# schema.net
KiCad netlist of a schematic drawn in EasyEDA
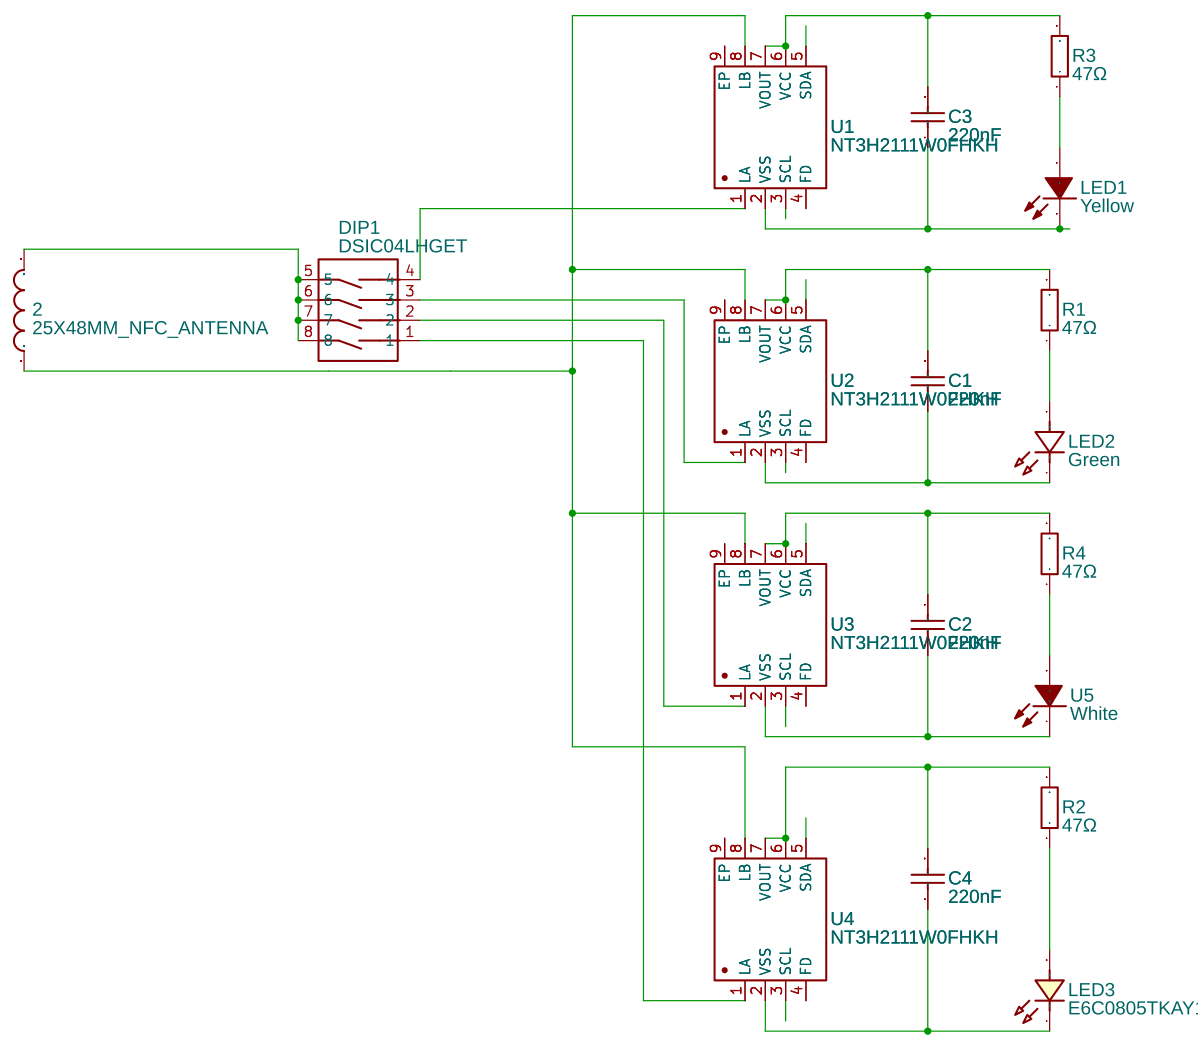
[diagram p0: schematic sheet]

(export (version "E")
  (design (tool "Eeschema 10.0.6"))
  (components
    (comp (ref "2") (value "25X48MM_NFC_ANTENNA") (libsource (lib "") (part "25X48MM_NFC_ANTENNA")))
    (comp (ref "C1")
      (value "220nF")
      (fields
        (field (name "Manufacturer Part") "CL10B224KA8NNNC")
        (field (name "Manufacturer") "SAMSUNG(三星)")
      )
      (libsource (lib "") (part "CL10B224KA8NNNC"))
    )
    (comp (ref "C2")
      (value "220nF")
      (fields
        (field (name "Manufacturer Part") "CL10B224KA8NNNC")
        (field (name "Manufacturer") "SAMSUNG(三星)")
      )
      (libsource (lib "") (part "CL10B224KA8NNNC"))
    )
    (comp (ref "C3")
      (value "220nF")
      (fields
        (field (name "Manufacturer Part") "CL10B224KA8NNNC")
        (field (name "Manufacturer") "SAMSUNG(三星)")
      )
      (libsource (lib "") (part "CL10B224KA8NNNC"))
    )
    (comp (ref "C4")
      (value "220nF")
      (fields
        (field (name "Manufacturer Part") "CL10B224KA8NNNC")
        (field (name "Manufacturer") "SAMSUNG(三星)")
      )
      (libsource (lib "") (part "CL10B224KA8NNNC"))
    )
    (comp (ref "DIP1")
      (value "DSIC04LHGET")
      (fields (field (name "Manufacturer") "YE"))
      (libsource (lib "") (part "DSIC04LHGET"))
    )
    (comp (ref "LED1")
      (value "Yellow")
      (fields (field (name "Manufacturer Part") "KT-0805黄灯") (field (name "Manufacturer") "KENTO"))
      (libsource (lib "") (part "17-21SUYC/TR8"))
    )
    (comp (ref "LED2")
      (value "Green")
      (fields (field (name "Manufacturer Part") "绿色0805封装贴片LED灯"))
      (libsource (lib "") (part "绿色0805封装贴片LED灯"))
    )
    (comp (ref "LED3")
      (value "E6C0805TKAY1UDA")
      (fields (field (name "Manufacturer") "ekinglux(亿晶源)"))
      (libsource (lib "") (part "E6C0805TKAY1UDA"))
    )
    (comp (ref "R1")
      (value "47Ω")
      (fields
        (field (name "Manufacturer Part") "0603WAF470JT5E")
        (field (name "Manufacturer") "UNI-ROYAL(厚声)")
      )
      (libsource (lib "") (part "0603WAF470JT5E"))
    )
    (comp (ref "R2")
      (value "47Ω")
      (fields
        (field (name "Manufacturer Part") "0603WAF470JT5E")
        (field (name "Manufacturer") "UNI-ROYAL(厚声)")
      )
      (libsource (lib "") (part "0603WAF470JT5E"))
    )
    (comp (ref "R3")
      (value "47Ω")
      (fields
        (field (name "Manufacturer Part") "0603WAF470JT5E")
        (field (name "Manufacturer") "UNI-ROYAL(厚声)")
      )
      (libsource (lib "") (part "0603WAF470JT5E"))
    )
    (comp (ref "R4")
      (value "47Ω")
      (fields
        (field (name "Manufacturer Part") "0603WAF470JT5E")
        (field (name "Manufacturer") "UNI-ROYAL(厚声)")
      )
      (libsource (lib "") (part "0603WAF470JT5E"))
    )
    (comp (ref "U1")
      (value "NT3H2111W0FHKH")
      (fields (field (name "Manufacturer") "NXP(恩智浦)"))
      (libsource (lib "") (part "NT3H2111W0FHKH"))
    )
    (comp (ref "U2")
      (value "NT3H2111W0FHKH")
      (fields (field (name "Manufacturer") "NXP(恩智浦)"))
      (libsource (lib "") (part "NT3H2111W0FHKH"))
    )
    (comp (ref "U3")
      (value "NT3H2111W0FHKH")
      (fields (field (name "Manufacturer") "NXP(恩智浦)"))
      (libsource (lib "") (part "NT3H2111W0FHKH"))
    )
    (comp (ref "U4")
      (value "NT3H2111W0FHKH")
      (fields (field (name "Manufacturer") "NXP(恩智浦)"))
      (libsource (lib "") (part "NT3H2111W0FHKH"))
    )
    (comp (ref "U5") (value "White") (libsource (lib "") (part "白光0805LED")))
  )
  (nets
    (net (code "1") (name "Net-(2-PadP$2)") (class "Default")
      (node (ref "2") (pin "P$2") (pinfunction "P$2_P$2") (pintype "bidirectional"))
      (node (ref "DIP1") (pin "5") (pinfunction "5_5") (pintype "unspecified"))
      (node (ref "DIP1") (pin "6") (pinfunction "6_6") (pintype "unspecified"))
      (node (ref "DIP1") (pin "7") (pinfunction "7_7") (pintype "unspecified"))
      (node (ref "DIP1") (pin "8") (pinfunction "8_8") (pintype "unspecified"))
    )
    (net (code "2") (name "Net-(LED1-+)") (class "Default")
      (node (ref "LED1") (pin "1") (pinfunction "+_1") (pintype "unspecified"))
      (node (ref "R3") (pin "1") (pinfunction "1_1") (pintype "input"))
    )
    (net (code "3") (name "Net-(LED1--)") (class "Default")
      (node (ref "C3") (pin "1") (pinfunction "1_1") (pintype "input"))
      (node (ref "LED1") (pin "2") (pinfunction "-_2") (pintype "unspecified"))
      (node (ref "U1") (pin "2") (pinfunction "VSS_2") (pintype "unspecified"))
    )
    (net (code "4") (name "Net-(LED2-A)") (class "Default")
      (node (ref "LED2") (pin "2") (pinfunction "A_2") (pintype "unspecified"))
      (node (ref "R1") (pin "1") (pinfunction "1_1") (pintype "input"))
    )
    (net (code "5") (name "Net-(LED2-K)") (class "Default")
      (node (ref "C1") (pin "1") (pinfunction "1_1") (pintype "input"))
      (node (ref "LED2") (pin "1") (pinfunction "K_1") (pintype "unspecified"))
      (node (ref "U2") (pin "2") (pinfunction "VSS_2") (pintype "unspecified"))
    )
    (net (code "6") (name "Net-(LED3-A)") (class "Default")
      (node (ref "LED3") (pin "2") (pinfunction "A_2") (pintype "unspecified"))
      (node (ref "R2") (pin "1") (pinfunction "1_1") (pintype "input"))
    )
    (net (code "7") (name "Net-(LED3-K)") (class "Default")
      (node (ref "C4") (pin "1") (pinfunction "1_1") (pintype "input"))
      (node (ref "LED3") (pin "1") (pinfunction "K_1") (pintype "unspecified"))
      (node (ref "U4") (pin "2") (pinfunction "VSS_2") (pintype "unspecified"))
    )
    (net (code "8") (name "Net-(U1-LA)") (class "Default")
      (node (ref "DIP1") (pin "4") (pinfunction "4_4") (pintype "unspecified"))
      (node (ref "U1") (pin "1") (pinfunction "LA_1") (pintype "unspecified"))
    )
    (net (code "9") (name "Net-(U1-LB)") (class "Default")
      (node (ref "2") (pin "P$1") (pinfunction "P$1_P$1") (pintype "bidirectional"))
      (node (ref "U1") (pin "8") (pinfunction "LB_8") (pintype "unspecified"))
      (node (ref "U2") (pin "8") (pinfunction "LB_8") (pintype "unspecified"))
      (node (ref "U3") (pin "8") (pinfunction "LB_8") (pintype "unspecified"))
      (node (ref "U4") (pin "8") (pinfunction "LB_8") (pintype "unspecified"))
    )
    (net (code "10") (name "Net-(U1-VCC)") (class "Default")
      (node (ref "C3") (pin "2") (pinfunction "2_2") (pintype "input"))
      (node (ref "R3") (pin "2") (pinfunction "2_2") (pintype "input"))
      (node (ref "U1") (pin "6") (pinfunction "VCC_6") (pintype "unspecified"))
      (node (ref "U1") (pin "7") (pinfunction "VOUT_7") (pintype "unspecified"))
    )
    (net (code "11") (name "Net-(U2-LA)") (class "Default")
      (node (ref "DIP1") (pin "3") (pinfunction "3_3") (pintype "unspecified"))
      (node (ref "U2") (pin "1") (pinfunction "LA_1") (pintype "unspecified"))
    )
    (net (code "12") (name "Net-(U2-VCC)") (class "Default")
      (node (ref "C1") (pin "2") (pinfunction "2_2") (pintype "input"))
      (node (ref "R1") (pin "2") (pinfunction "2_2") (pintype "input"))
      (node (ref "U2") (pin "6") (pinfunction "VCC_6") (pintype "unspecified"))
      (node (ref "U2") (pin "7") (pinfunction "VOUT_7") (pintype "unspecified"))
    )
    (net (code "13") (name "Net-(U3-LA)") (class "Default")
      (node (ref "DIP1") (pin "2") (pinfunction "2_2") (pintype "unspecified"))
      (node (ref "U3") (pin "1") (pinfunction "LA_1") (pintype "unspecified"))
    )
    (net (code "14") (name "Net-(U3-VCC)") (class "Default")
      (node (ref "C2") (pin "2") (pinfunction "2_2") (pintype "input"))
      (node (ref "R4") (pin "2") (pinfunction "2_2") (pintype "input"))
      (node (ref "U3") (pin "6") (pinfunction "VCC_6") (pintype "unspecified"))
      (node (ref "U3") (pin "7") (pinfunction "VOUT_7") (pintype "unspecified"))
    )
    (net (code "15") (name "Net-(U3-VSS)") (class "Default")
      (node (ref "C2") (pin "1") (pinfunction "1_1") (pintype "input"))
      (node (ref "U3") (pin "2") (pinfunction "VSS_2") (pintype "unspecified"))
      (node (ref "U5") (pin "1") (pinfunction "C_1") (pintype "unspecified"))
    )
    (net (code "16") (name "Net-(U4-LA)") (class "Default")
      (node (ref "DIP1") (pin "1") (pinfunction "1_1") (pintype "unspecified"))
      (node (ref "U4") (pin "1") (pinfunction "LA_1") (pintype "unspecified"))
    )
    (net (code "17") (name "Net-(U4-VCC)") (class "Default")
      (node (ref "C4") (pin "2") (pinfunction "2_2") (pintype "input"))
      (node (ref "R2") (pin "2") (pinfunction "2_2") (pintype "input"))
      (node (ref "U4") (pin "6") (pinfunction "VCC_6") (pintype "unspecified"))
      (node (ref "U4") (pin "7") (pinfunction "VOUT_7") (pintype "unspecified"))
    )
    (net (code "18") (name "Net-(U5-A)") (class "Default")
      (node (ref "R4") (pin "1") (pinfunction "1_1") (pintype "input"))
      (node (ref "U5") (pin "2") (pinfunction "A_2") (pintype "unspecified"))
    )
    (net (code "19") (name "unconnected-(U1-EP-Pad9)") (class "Default")
      (node (ref "U1") (pin "9") (pinfunction "EP_9") (pintype "unspecified"))
    )
    (net (code "20") (name "unconnected-(U1-FD-Pad4)") (class "Default")
      (node (ref "U1") (pin "4") (pinfunction "FD_4") (pintype "unspecified"))
    )
    (net (code "21") (name "unconnected-(U1-SCL-Pad3)") (class "Default")
      (node (ref "U1") (pin "3") (pinfunction "SCL_3") (pintype "unspecified"))
    )
    (net (code "22") (name "unconnected-(U1-SDA-Pad5)") (class "Default")
      (node (ref "U1") (pin "5") (pinfunction "SDA_5") (pintype "unspecified"))
    )
    (net (code "23") (name "unconnected-(U2-EP-Pad9)") (class "Default")
      (node (ref "U2") (pin "9") (pinfunction "EP_9") (pintype "unspecified"))
    )
    (net (code "24") (name "unconnected-(U2-FD-Pad4)") (class "Default")
      (node (ref "U2") (pin "4") (pinfunction "FD_4") (pintype "unspecified"))
    )
    (net (code "25") (name "unconnected-(U2-SCL-Pad3)") (class "Default")
      (node (ref "U2") (pin "3") (pinfunction "SCL_3") (pintype "unspecified"))
    )
    (net (code "26") (name "unconnected-(U2-SDA-Pad5)") (class "Default")
      (node (ref "U2") (pin "5") (pinfunction "SDA_5") (pintype "unspecified"))
    )
    (net (code "27") (name "unconnected-(U3-EP-Pad9)") (class "Default")
      (node (ref "U3") (pin "9") (pinfunction "EP_9") (pintype "unspecified"))
    )
    (net (code "28") (name "unconnected-(U3-FD-Pad4)") (class "Default")
      (node (ref "U3") (pin "4") (pinfunction "FD_4") (pintype "unspecified"))
    )
    (net (code "29") (name "unconnected-(U3-SCL-Pad3)") (class "Default")
      (node (ref "U3") (pin "3") (pinfunction "SCL_3") (pintype "unspecified"))
    )
    (net (code "30") (name "unconnected-(U3-SDA-Pad5)") (class "Default")
      (node (ref "U3") (pin "5") (pinfunction "SDA_5") (pintype "unspecified"))
    )
    (net (code "31") (name "unconnected-(U4-EP-Pad9)") (class "Default")
      (node (ref "U4") (pin "9") (pinfunction "EP_9") (pintype "unspecified"))
    )
    (net (code "32") (name "unconnected-(U4-FD-Pad4)") (class "Default")
      (node (ref "U4") (pin "4") (pinfunction "FD_4") (pintype "unspecified"))
    )
    (net (code "33") (name "unconnected-(U4-SCL-Pad3)") (class "Default")
      (node (ref "U4") (pin "3") (pinfunction "SCL_3") (pintype "unspecified"))
    )
    (net (code "34") (name "unconnected-(U4-SDA-Pad5)") (class "Default")
      (node (ref "U4") (pin "5") (pinfunction "SDA_5") (pintype "unspecified"))
    )
  )
)
